# bms1.net
KiCad netlist of a schematic drawn in EAGLE
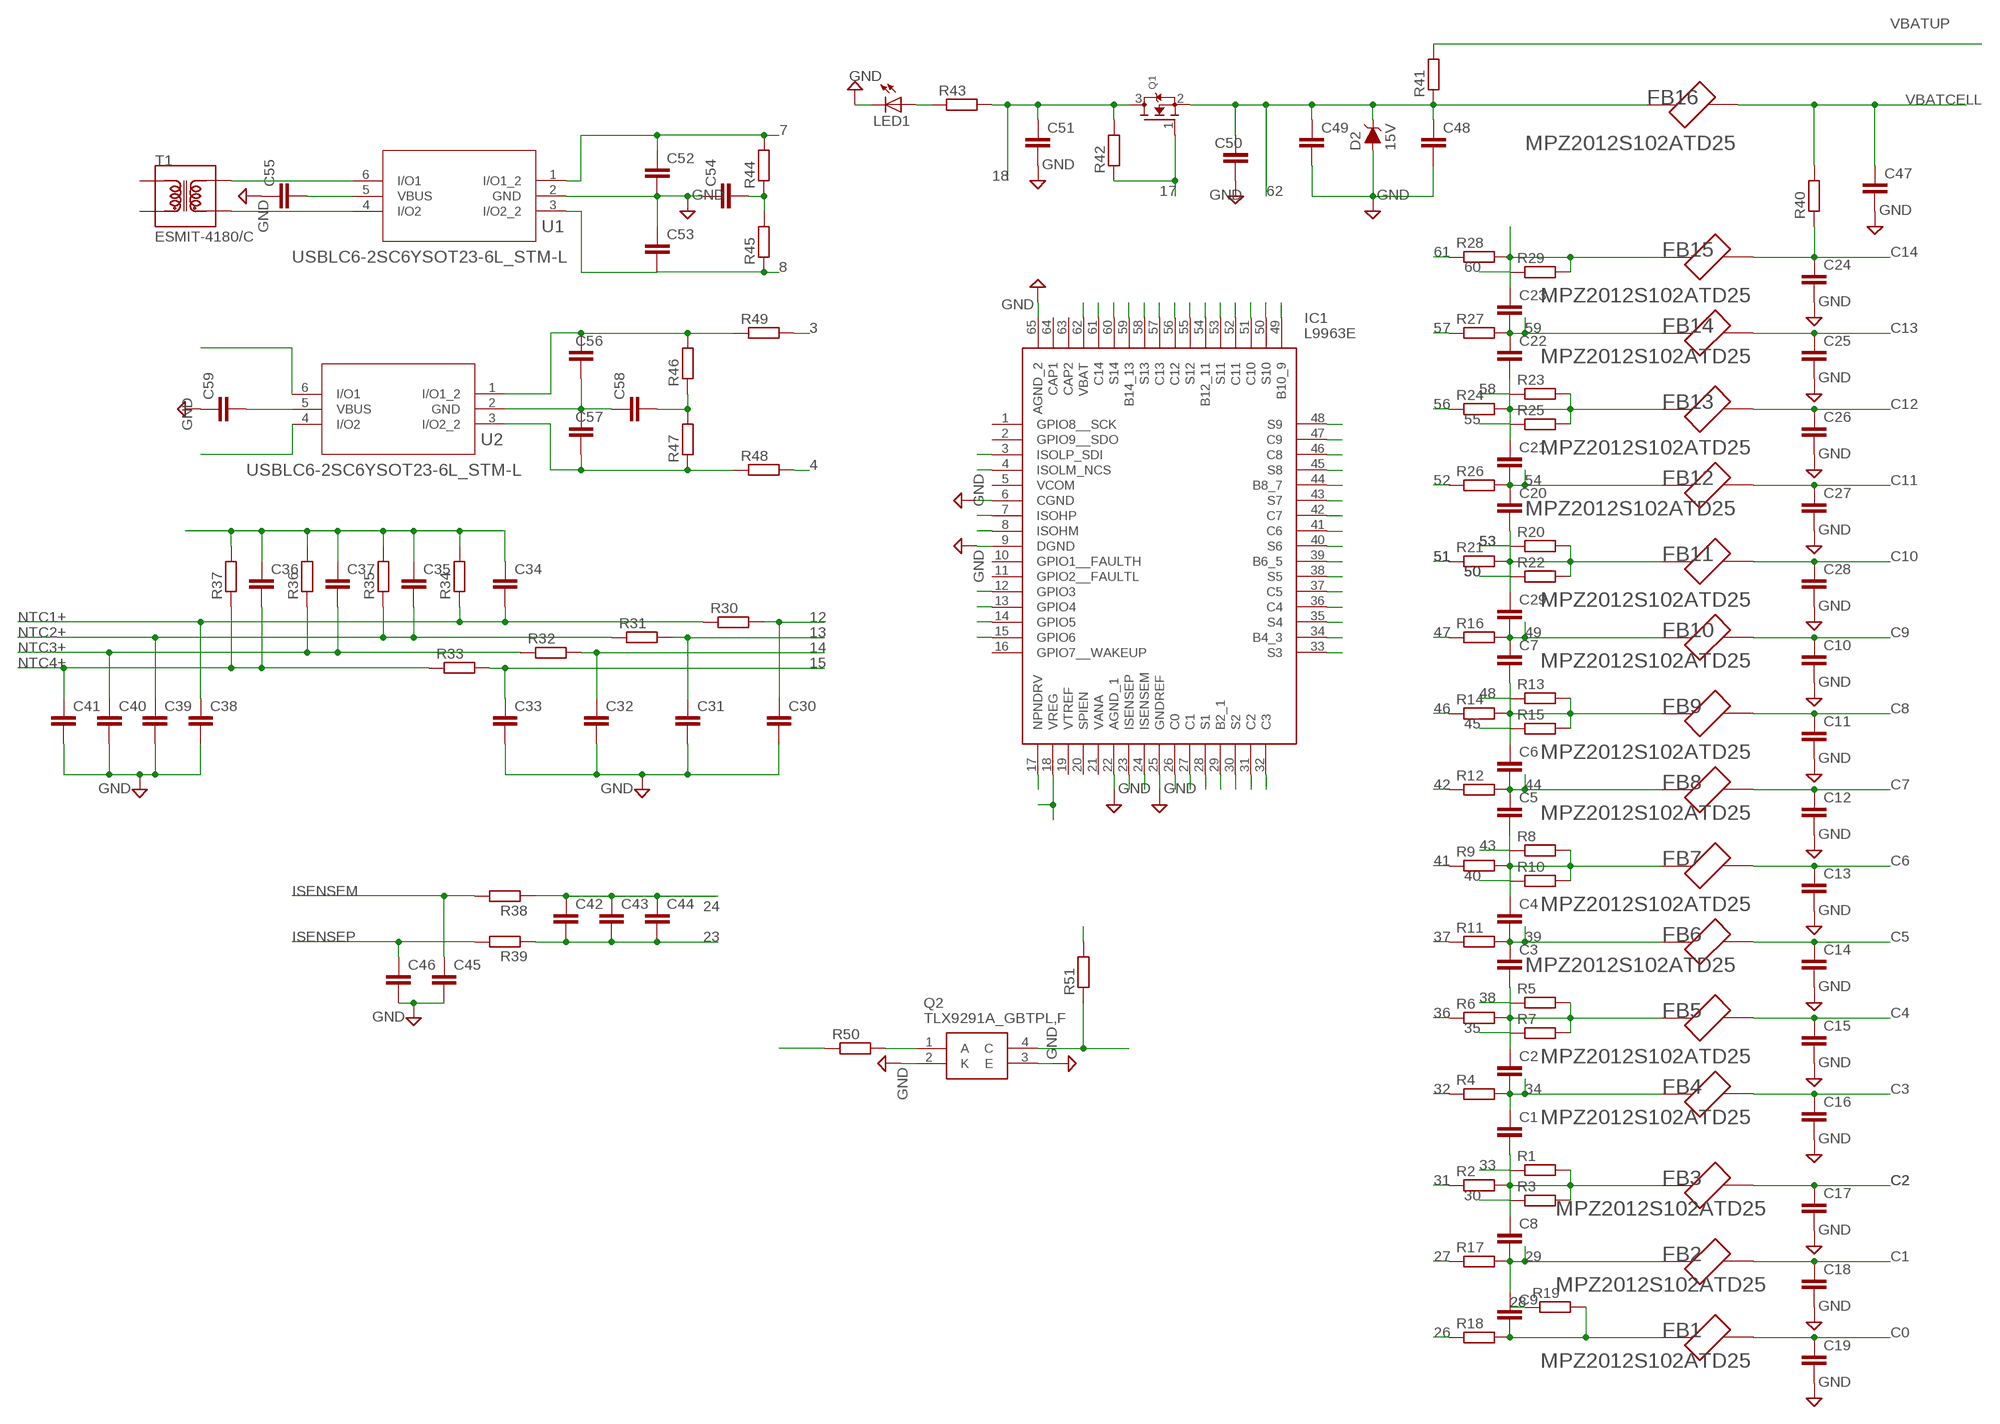
[diagram p0: schematic, sheet 1]

(export (version "E")
  (design (tool "Eeschema 10.0.6"))
  (components
    (comp (ref "C1")
      (value "C-EUC0402K")
      (footprint "eagle-import:C0402K")
      (libsource (lib "eagle-import") (part "C-EUC0402K"))
    )
    (comp (ref "C2")
      (value "C-EUC0402K")
      (footprint "eagle-import:C0402K")
      (libsource (lib "eagle-import") (part "C-EUC0402K"))
    )
    (comp (ref "C3")
      (value "C-EUC0402K")
      (footprint "eagle-import:C0402K")
      (libsource (lib "eagle-import") (part "C-EUC0402K"))
    )
    (comp (ref "C4")
      (value "C-EUC0402K")
      (footprint "eagle-import:C0402K")
      (libsource (lib "eagle-import") (part "C-EUC0402K"))
    )
    (comp (ref "C5")
      (value "C-EUC0402K")
      (footprint "eagle-import:C0402K")
      (libsource (lib "eagle-import") (part "C-EUC0402K"))
    )
    (comp (ref "C6")
      (value "C-EUC0402K")
      (footprint "eagle-import:C0402K")
      (libsource (lib "eagle-import") (part "C-EUC0402K"))
    )
    (comp (ref "C7")
      (value "C-EUC0402K")
      (footprint "eagle-import:C0402K")
      (libsource (lib "eagle-import") (part "C-EUC0402K"))
    )
    (comp (ref "C8")
      (value "C-EUC0402K")
      (footprint "eagle-import:C0402K")
      (libsource (lib "eagle-import") (part "C-EUC0402K"))
    )
    (comp (ref "C9")
      (value "C-EUC0402K")
      (footprint "eagle-import:C0402K")
      (libsource (lib "eagle-import") (part "C-EUC0402K"))
    )
    (comp (ref "C10")
      (value "C-EUC0402K")
      (footprint "eagle-import:C0402K")
      (libsource (lib "eagle-import") (part "C-EUC0402K"))
    )
    (comp (ref "C11")
      (value "C-EUC0402K")
      (footprint "eagle-import:C0402K")
      (libsource (lib "eagle-import") (part "C-EUC0402K"))
    )
    (comp (ref "C12")
      (value "C-EUC0402K")
      (footprint "eagle-import:C0402K")
      (libsource (lib "eagle-import") (part "C-EUC0402K"))
    )
    (comp (ref "C13")
      (value "C-EUC0402K")
      (footprint "eagle-import:C0402K")
      (libsource (lib "eagle-import") (part "C-EUC0402K"))
    )
    (comp (ref "C14")
      (value "C-EUC0402K")
      (footprint "eagle-import:C0402K")
      (libsource (lib "eagle-import") (part "C-EUC0402K"))
    )
    (comp (ref "C15")
      (value "C-EUC0402K")
      (footprint "eagle-import:C0402K")
      (libsource (lib "eagle-import") (part "C-EUC0402K"))
    )
    (comp (ref "C16")
      (value "C-EUC0402K")
      (footprint "eagle-import:C0402K")
      (libsource (lib "eagle-import") (part "C-EUC0402K"))
    )
    (comp (ref "C17")
      (value "C-EUC0402K")
      (footprint "eagle-import:C0402K")
      (libsource (lib "eagle-import") (part "C-EUC0402K"))
    )
    (comp (ref "C18")
      (value "C-EUC0402K")
      (footprint "eagle-import:C0402K")
      (libsource (lib "eagle-import") (part "C-EUC0402K"))
    )
    (comp (ref "C19")
      (value "C-EUC0402K")
      (footprint "eagle-import:C0402K")
      (libsource (lib "eagle-import") (part "C-EUC0402K"))
    )
    (comp (ref "C20")
      (value "C-EUC0402K")
      (footprint "eagle-import:C0402K")
      (libsource (lib "eagle-import") (part "C-EUC0402K"))
    )
    (comp (ref "C21")
      (value "C-EUC0402K")
      (footprint "eagle-import:C0402K")
      (libsource (lib "eagle-import") (part "C-EUC0402K"))
    )
    (comp (ref "C22")
      (value "C-EUC0402K")
      (footprint "eagle-import:C0402K")
      (libsource (lib "eagle-import") (part "C-EUC0402K"))
    )
    (comp (ref "C23")
      (value "C-EUC0402K")
      (footprint "eagle-import:C0402K")
      (libsource (lib "eagle-import") (part "C-EUC0402K"))
    )
    (comp (ref "C24")
      (value "C-EUC0402K")
      (footprint "eagle-import:C0402K")
      (libsource (lib "eagle-import") (part "C-EUC0402K"))
    )
    (comp (ref "C25")
      (value "C-EUC0402K")
      (footprint "eagle-import:C0402K")
      (libsource (lib "eagle-import") (part "C-EUC0402K"))
    )
    (comp (ref "C26")
      (value "C-EUC0402K")
      (footprint "eagle-import:C0402K")
      (libsource (lib "eagle-import") (part "C-EUC0402K"))
    )
    (comp (ref "C27")
      (value "C-EUC0402K")
      (footprint "eagle-import:C0402K")
      (libsource (lib "eagle-import") (part "C-EUC0402K"))
    )
    (comp (ref "C28")
      (value "C-EUC0402K")
      (footprint "eagle-import:C0402K")
      (libsource (lib "eagle-import") (part "C-EUC0402K"))
    )
    (comp (ref "C29")
      (value "C-EUC0402K")
      (footprint "eagle-import:C0402K")
      (libsource (lib "eagle-import") (part "C-EUC0402K"))
    )
    (comp (ref "C30")
      (value "C-EUC0402K")
      (footprint "eagle-import:C0402K")
      (libsource (lib "eagle-import") (part "C-EUC0402K"))
    )
    (comp (ref "C31")
      (value "C-EUC0402K")
      (footprint "eagle-import:C0402K")
      (libsource (lib "eagle-import") (part "C-EUC0402K"))
    )
    (comp (ref "C32")
      (value "C-EUC0402K")
      (footprint "eagle-import:C0402K")
      (libsource (lib "eagle-import") (part "C-EUC0402K"))
    )
    (comp (ref "C33")
      (value "C-EUC0402K")
      (footprint "eagle-import:C0402K")
      (libsource (lib "eagle-import") (part "C-EUC0402K"))
    )
    (comp (ref "C34")
      (value "C-EUC0402K")
      (footprint "eagle-import:C0402K")
      (libsource (lib "eagle-import") (part "C-EUC0402K"))
    )
    (comp (ref "C35")
      (value "C-EUC0402K")
      (footprint "eagle-import:C0402K")
      (libsource (lib "eagle-import") (part "C-EUC0402K"))
    )
    (comp (ref "C36")
      (value "C-EUC0402K")
      (footprint "eagle-import:C0402K")
      (libsource (lib "eagle-import") (part "C-EUC0402K"))
    )
    (comp (ref "C37")
      (value "C-EUC0402K")
      (footprint "eagle-import:C0402K")
      (libsource (lib "eagle-import") (part "C-EUC0402K"))
    )
    (comp (ref "C38")
      (value "C-EUC0402K")
      (footprint "eagle-import:C0402K")
      (libsource (lib "eagle-import") (part "C-EUC0402K"))
    )
    (comp (ref "C39")
      (value "C-EUC0402K")
      (footprint "eagle-import:C0402K")
      (libsource (lib "eagle-import") (part "C-EUC0402K"))
    )
    (comp (ref "C40")
      (value "C-EUC0402K")
      (footprint "eagle-import:C0402K")
      (libsource (lib "eagle-import") (part "C-EUC0402K"))
    )
    (comp (ref "C41")
      (value "C-EUC0402K")
      (footprint "eagle-import:C0402K")
      (libsource (lib "eagle-import") (part "C-EUC0402K"))
    )
    (comp (ref "C42")
      (value "C-EUC0402K")
      (footprint "eagle-import:C0402K")
      (libsource (lib "eagle-import") (part "C-EUC0402K"))
    )
    (comp (ref "C43")
      (value "C-EUC0402K")
      (footprint "eagle-import:C0402K")
      (libsource (lib "eagle-import") (part "C-EUC0402K"))
    )
    (comp (ref "C44")
      (value "C-EUC0402K")
      (footprint "eagle-import:C0402K")
      (libsource (lib "eagle-import") (part "C-EUC0402K"))
    )
    (comp (ref "C45")
      (value "C-EUC0402K")
      (footprint "eagle-import:C0402K")
      (libsource (lib "eagle-import") (part "C-EUC0402K"))
    )
    (comp (ref "C46")
      (value "C-EUC0402K")
      (footprint "eagle-import:C0402K")
      (libsource (lib "eagle-import") (part "C-EUC0402K"))
    )
    (comp (ref "C47")
      (value "C-EUC0402K")
      (footprint "eagle-import:C0402K")
      (libsource (lib "eagle-import") (part "C-EUC0402K"))
    )
    (comp (ref "C48")
      (value "C-EUC0402K")
      (footprint "eagle-import:C0402K")
      (libsource (lib "eagle-import") (part "C-EUC0402K"))
    )
    (comp (ref "C49")
      (value "C-EUC0402K")
      (footprint "eagle-import:C0402K")
      (libsource (lib "eagle-import") (part "C-EUC0402K"))
    )
    (comp (ref "C50")
      (value "C-EUC0402K")
      (footprint "eagle-import:C0402K")
      (libsource (lib "eagle-import") (part "C-EUC0402K"))
    )
    (comp (ref "C51")
      (value "C-EUC0402K")
      (footprint "eagle-import:C0402K")
      (libsource (lib "eagle-import") (part "C-EUC0402K"))
    )
    (comp (ref "C52")
      (value "C-EUC0402K")
      (footprint "eagle-import:C0402K")
      (libsource (lib "eagle-import") (part "C-EUC0402K"))
    )
    (comp (ref "C53")
      (value "C-EUC0402K")
      (footprint "eagle-import:C0402K")
      (libsource (lib "eagle-import") (part "C-EUC0402K"))
    )
    (comp (ref "C54")
      (value "C-EUC0402K")
      (footprint "eagle-import:C0402K")
      (libsource (lib "eagle-import") (part "C-EUC0402K"))
    )
    (comp (ref "C55")
      (value "C-EUC0402K")
      (footprint "eagle-import:C0402K")
      (libsource (lib "eagle-import") (part "C-EUC0402K"))
    )
    (comp (ref "C56")
      (value "C-EUC0402K")
      (footprint "eagle-import:C0402K")
      (libsource (lib "eagle-import") (part "C-EUC0402K"))
    )
    (comp (ref "C57")
      (value "C-EUC0402K")
      (footprint "eagle-import:C0402K")
      (libsource (lib "eagle-import") (part "C-EUC0402K"))
    )
    (comp (ref "C58")
      (value "C-EUC0402K")
      (footprint "eagle-import:C0402K")
      (libsource (lib "eagle-import") (part "C-EUC0402K"))
    )
    (comp (ref "C59")
      (value "C-EUC0402K")
      (footprint "eagle-import:C0402K")
      (libsource (lib "eagle-import") (part "C-EUC0402K"))
    )
    (comp (ref "D2")
      (value "15V")
      (footprint "eagle-import:PANASONIC_SMINI2-F5-B")
      (libsource (lib "eagle-import") (part "DIODE-ZENER-DZ2J150M0L"))
    )
    (comp (ref "FB1")
      (value "MPZ2012S102ATD25")
      (footprint "eagle-import:BEADC2012X105N")
      (fields (field (name "MF") "TDK"))
      (libsource (lib "eagle-import") (part "MPZ2012S102ATD25"))
    )
    (comp (ref "FB2")
      (value "MPZ2012S102ATD25")
      (footprint "eagle-import:BEADC2012X105N")
      (fields (field (name "MF") "TDK"))
      (libsource (lib "eagle-import") (part "MPZ2012S102ATD25"))
    )
    (comp (ref "FB3")
      (value "MPZ2012S102ATD25")
      (footprint "eagle-import:BEADC2012X105N")
      (fields (field (name "MF") "TDK"))
      (libsource (lib "eagle-import") (part "MPZ2012S102ATD25"))
    )
    (comp (ref "FB4")
      (value "MPZ2012S102ATD25")
      (footprint "eagle-import:BEADC2012X105N")
      (fields (field (name "MF") "TDK"))
      (libsource (lib "eagle-import") (part "MPZ2012S102ATD25"))
    )
    (comp (ref "FB5")
      (value "MPZ2012S102ATD25")
      (footprint "eagle-import:BEADC2012X105N")
      (fields (field (name "MF") "TDK"))
      (libsource (lib "eagle-import") (part "MPZ2012S102ATD25"))
    )
    (comp (ref "FB6")
      (value "MPZ2012S102ATD25")
      (footprint "eagle-import:BEADC2012X105N")
      (fields (field (name "MF") "TDK"))
      (libsource (lib "eagle-import") (part "MPZ2012S102ATD25"))
    )
    (comp (ref "FB7")
      (value "MPZ2012S102ATD25")
      (footprint "eagle-import:BEADC2012X105N")
      (fields (field (name "MF") "TDK"))
      (libsource (lib "eagle-import") (part "MPZ2012S102ATD25"))
    )
    (comp (ref "FB8")
      (value "MPZ2012S102ATD25")
      (footprint "eagle-import:BEADC2012X105N")
      (fields (field (name "MF") "TDK"))
      (libsource (lib "eagle-import") (part "MPZ2012S102ATD25"))
    )
    (comp (ref "FB9")
      (value "MPZ2012S102ATD25")
      (footprint "eagle-import:BEADC2012X105N")
      (fields (field (name "MF") "TDK"))
      (libsource (lib "eagle-import") (part "MPZ2012S102ATD25"))
    )
    (comp (ref "FB10")
      (value "MPZ2012S102ATD25")
      (footprint "eagle-import:BEADC2012X105N")
      (fields (field (name "MF") "TDK"))
      (libsource (lib "eagle-import") (part "MPZ2012S102ATD25"))
    )
    (comp (ref "FB11")
      (value "MPZ2012S102ATD25")
      (footprint "eagle-import:BEADC2012X105N")
      (fields (field (name "MF") "TDK"))
      (libsource (lib "eagle-import") (part "MPZ2012S102ATD25"))
    )
    (comp (ref "FB12")
      (value "MPZ2012S102ATD25")
      (footprint "eagle-import:BEADC2012X105N")
      (fields (field (name "MF") "TDK"))
      (libsource (lib "eagle-import") (part "MPZ2012S102ATD25"))
    )
    (comp (ref "FB13")
      (value "MPZ2012S102ATD25")
      (footprint "eagle-import:BEADC2012X105N")
      (fields (field (name "MF") "TDK"))
      (libsource (lib "eagle-import") (part "MPZ2012S102ATD25"))
    )
    (comp (ref "FB14")
      (value "MPZ2012S102ATD25")
      (footprint "eagle-import:BEADC2012X105N")
      (fields (field (name "MF") "TDK"))
      (libsource (lib "eagle-import") (part "MPZ2012S102ATD25"))
    )
    (comp (ref "FB15")
      (value "MPZ2012S102ATD25")
      (footprint "eagle-import:BEADC2012X105N")
      (fields (field (name "MF") "TDK"))
      (libsource (lib "eagle-import") (part "MPZ2012S102ATD25"))
    )
    (comp (ref "FB16")
      (value "MPZ2012S102ATD25")
      (footprint "eagle-import:BEADC2012X105N")
      (fields (field (name "MF") "TDK"))
      (libsource (lib "eagle-import") (part "MPZ2012S102ATD25"))
    )
    (comp (ref "IC1")
      (value "L9963E")
      (footprint "eagle-import:QFP50P1200X1200X120-65N")
      (fields (field (name "MOUSER_PART_NUMBER") "511-L9963E"))
      (libsource (lib "eagle-import") (part "L9963E"))
    )
    (comp (ref "LED1")
      (value "LED")
      (footprint "eagle-import:SMARTLED-TTW")
      (libsource (lib "eagle-import") (part "LED"))
    )
    (comp (ref "Q1")
      (value "MOSFET-NREFLOW")
      (footprint "eagle-import:SOT23")
      (libsource (lib "eagle-import") (part "MOSFET-NREFLOW"))
    )
    (comp (ref "Q2")
      (value "TLX9291A_GBTPL,F")
      (footprint "eagle-import:SOIC127P700X230-4N")
      (fields
        (field (name "MANUFACTURER_PART_NUMBER") "TLX9291A(GBTPL,F")
        (field (name "MOUSER_PART_NUMBER") "757-TLX9291AGBTPLF")
      )
      (libsource (lib "eagle-import") (part "TLX9291A_GBTPL,F"))
    )
    (comp (ref "R1")
      (value "R-EU_R0603")
      (footprint "eagle-import:R0603")
      (libsource (lib "eagle-import") (part "R-EU_R0603"))
    )
    (comp (ref "R2")
      (value "R-EU_R0603")
      (footprint "eagle-import:R0603")
      (libsource (lib "eagle-import") (part "R-EU_R0603"))
    )
    (comp (ref "R3")
      (value "R-EU_R0603")
      (footprint "eagle-import:R0603")
      (libsource (lib "eagle-import") (part "R-EU_R0603"))
    )
    (comp (ref "R4")
      (value "R-EU_R0603")
      (footprint "eagle-import:R0603")
      (libsource (lib "eagle-import") (part "R-EU_R0603"))
    )
    (comp (ref "R5")
      (value "R-EU_R0603")
      (footprint "eagle-import:R0603")
      (libsource (lib "eagle-import") (part "R-EU_R0603"))
    )
    (comp (ref "R6")
      (value "R-EU_R0603")
      (footprint "eagle-import:R0603")
      (libsource (lib "eagle-import") (part "R-EU_R0603"))
    )
    (comp (ref "R7")
      (value "R-EU_R0603")
      (footprint "eagle-import:R0603")
      (libsource (lib "eagle-import") (part "R-EU_R0603"))
    )
    (comp (ref "R8")
      (value "R-EU_R0603")
      (footprint "eagle-import:R0603")
      (libsource (lib "eagle-import") (part "R-EU_R0603"))
    )
    (comp (ref "R9")
      (value "R-EU_R0603")
      (footprint "eagle-import:R0603")
      (libsource (lib "eagle-import") (part "R-EU_R0603"))
    )
    (comp (ref "R10")
      (value "R-EU_R0603")
      (footprint "eagle-import:R0603")
      (libsource (lib "eagle-import") (part "R-EU_R0603"))
    )
    (comp (ref "R11")
      (value "R-EU_R0603")
      (footprint "eagle-import:R0603")
      (libsource (lib "eagle-import") (part "R-EU_R0603"))
    )
    (comp (ref "R12")
      (value "R-EU_R0603")
      (footprint "eagle-import:R0603")
      (libsource (lib "eagle-import") (part "R-EU_R0603"))
    )
    (comp (ref "R13")
      (value "R-EU_R0603")
      (footprint "eagle-import:R0603")
      (libsource (lib "eagle-import") (part "R-EU_R0603"))
    )
    (comp (ref "R14")
      (value "R-EU_R0603")
      (footprint "eagle-import:R0603")
      (libsource (lib "eagle-import") (part "R-EU_R0603"))
    )
    (comp (ref "R15")
      (value "R-EU_R0603")
      (footprint "eagle-import:R0603")
      (libsource (lib "eagle-import") (part "R-EU_R0603"))
    )
    (comp (ref "R16")
      (value "R-EU_R0603")
      (footprint "eagle-import:R0603")
      (libsource (lib "eagle-import") (part "R-EU_R0603"))
    )
    (comp (ref "R17")
      (value "R-EU_R0603")
      (footprint "eagle-import:R0603")
      (libsource (lib "eagle-import") (part "R-EU_R0603"))
    )
    (comp (ref "R18")
      (value "R-EU_R0603")
      (footprint "eagle-import:R0603")
      (libsource (lib "eagle-import") (part "R-EU_R0603"))
    )
    (comp (ref "R19")
      (value "R-EU_R0603")
      (footprint "eagle-import:R0603")
      (libsource (lib "eagle-import") (part "R-EU_R0603"))
    )
    (comp (ref "R20")
      (value "R-EU_R0603")
      (footprint "eagle-import:R0603")
      (libsource (lib "eagle-import") (part "R-EU_R0603"))
    )
    (comp (ref "R21")
      (value "R-EU_R0603")
      (footprint "eagle-import:R0603")
      (libsource (lib "eagle-import") (part "R-EU_R0603"))
    )
    (comp (ref "R22")
      (value "R-EU_R0603")
      (footprint "eagle-import:R0603")
      (libsource (lib "eagle-import") (part "R-EU_R0603"))
    )
    (comp (ref "R23")
      (value "R-EU_R0603")
      (footprint "eagle-import:R0603")
      (libsource (lib "eagle-import") (part "R-EU_R0603"))
    )
    (comp (ref "R24")
      (value "R-EU_R0603")
      (footprint "eagle-import:R0603")
      (libsource (lib "eagle-import") (part "R-EU_R0603"))
    )
    (comp (ref "R25")
      (value "R-EU_R0603")
      (footprint "eagle-import:R0603")
      (libsource (lib "eagle-import") (part "R-EU_R0603"))
    )
    (comp (ref "R26")
      (value "R-EU_R0603")
      (footprint "eagle-import:R0603")
      (libsource (lib "eagle-import") (part "R-EU_R0603"))
    )
    (comp (ref "R27")
      (value "R-EU_R0603")
      (footprint "eagle-import:R0603")
      (libsource (lib "eagle-import") (part "R-EU_R0603"))
    )
    (comp (ref "R28")
      (value "R-EU_R0603")
      (footprint "eagle-import:R0603")
      (libsource (lib "eagle-import") (part "R-EU_R0603"))
    )
    (comp (ref "R29")
      (value "R-EU_R0603")
      (footprint "eagle-import:R0603")
      (libsource (lib "eagle-import") (part "R-EU_R0603"))
    )
    (comp (ref "R30")
      (value "R-EU_R0603")
      (footprint "eagle-import:R0603")
      (libsource (lib "eagle-import") (part "R-EU_R0603"))
    )
    (comp (ref "R31")
      (value "R-EU_R0603")
      (footprint "eagle-import:R0603")
      (libsource (lib "eagle-import") (part "R-EU_R0603"))
    )
    (comp (ref "R32")
      (value "R-EU_R0603")
      (footprint "eagle-import:R0603")
      (libsource (lib "eagle-import") (part "R-EU_R0603"))
    )
    (comp (ref "R33")
      (value "R-EU_R0603")
      (footprint "eagle-import:R0603")
      (libsource (lib "eagle-import") (part "R-EU_R0603"))
    )
    (comp (ref "R34")
      (value "R-EU_R0603")
      (footprint "eagle-import:R0603")
      (libsource (lib "eagle-import") (part "R-EU_R0603"))
    )
    (comp (ref "R35")
      (value "R-EU_R0603")
      (footprint "eagle-import:R0603")
      (libsource (lib "eagle-import") (part "R-EU_R0603"))
    )
    (comp (ref "R36")
      (value "R-EU_R0603")
      (footprint "eagle-import:R0603")
      (libsource (lib "eagle-import") (part "R-EU_R0603"))
    )
    (comp (ref "R37")
      (value "R-EU_R0603")
      (footprint "eagle-import:R0603")
      (libsource (lib "eagle-import") (part "R-EU_R0603"))
    )
    (comp (ref "R38")
      (value "R-EU_R0603")
      (footprint "eagle-import:R0603")
      (libsource (lib "eagle-import") (part "R-EU_R0603"))
    )
    (comp (ref "R39")
      (value "R-EU_R0603")
      (footprint "eagle-import:R0603")
      (libsource (lib "eagle-import") (part "R-EU_R0603"))
    )
    (comp (ref "R40")
      (value "R-EU_R0603")
      (footprint "eagle-import:R0603")
      (libsource (lib "eagle-import") (part "R-EU_R0603"))
    )
    (comp (ref "R41")
      (value "R-EU_R0603")
      (footprint "eagle-import:R0603")
      (libsource (lib "eagle-import") (part "R-EU_R0603"))
    )
    (comp (ref "R42")
      (value "R-EU_R0603")
      (footprint "eagle-import:R0603")
      (libsource (lib "eagle-import") (part "R-EU_R0603"))
    )
    (comp (ref "R43")
      (value "R-EU_R0603")
      (footprint "eagle-import:R0603")
      (libsource (lib "eagle-import") (part "R-EU_R0603"))
    )
    (comp (ref "R44")
      (value "R-EU_R0603")
      (footprint "eagle-import:R0603")
      (libsource (lib "eagle-import") (part "R-EU_R0603"))
    )
    (comp (ref "R45")
      (value "R-EU_R0603")
      (footprint "eagle-import:R0603")
      (libsource (lib "eagle-import") (part "R-EU_R0603"))
    )
    (comp (ref "R46")
      (value "R-EU_R0603")
      (footprint "eagle-import:R0603")
      (libsource (lib "eagle-import") (part "R-EU_R0603"))
    )
    (comp (ref "R47")
      (value "R-EU_R0603")
      (footprint "eagle-import:R0603")
      (libsource (lib "eagle-import") (part "R-EU_R0603"))
    )
    (comp (ref "R48")
      (value "R-EU_R0603")
      (footprint "eagle-import:R0603")
      (libsource (lib "eagle-import") (part "R-EU_R0603"))
    )
    (comp (ref "R49")
      (value "R-EU_R0603")
      (footprint "eagle-import:R0603")
      (libsource (lib "eagle-import") (part "R-EU_R0603"))
    )
    (comp (ref "R50")
      (value "R-EU_M0805")
      (footprint "eagle-import:M0805")
      (libsource (lib "eagle-import") (part "R-EU_M0805"))
    )
    (comp (ref "R51")
      (value "R-EU_M0805")
      (footprint "eagle-import:M0805")
      (libsource (lib "eagle-import") (part "R-EU_M0805"))
    )
    (comp (ref "T1")
      (value "ESMIT-4180/C")
      (footprint "eagle-import:XFMR_ESMIT-4180_C")
      (fields (field (name "MF") "Sumida America"))
      (libsource (lib "eagle-import") (part "ESMIT-4180/C"))
    )
    (comp (ref "U1")
      (value "USBLC6-2SC6YSOT23-6L_STM-L")
      (footprint "eagle-import:SOT23-6L_STM-L")
      (fields
        (field (name "MANUFACTURER_PART_NUMBER") "USBLC6-2SC6Y")
        (field (name "COPYRIGHT") "Copyright (C) 2021 Ultra Librarian. All rights reserved.")
      )
      (libsource (lib "eagle-import") (part "USBLC6-2SC6YSOT23-6L_STM-L"))
    )
    (comp (ref "U2")
      (value "USBLC6-2SC6YSOT23-6L_STM-L")
      (footprint "eagle-import:SOT23-6L_STM-L")
      (fields
        (field (name "MANUFACTURER_PART_NUMBER") "USBLC6-2SC6Y")
        (field (name "COPYRIGHT") "Copyright (C) 2021 Ultra Librarian. All rights reserved.")
      )
      (libsource (lib "eagle-import") (part "USBLC6-2SC6YSOT23-6L_STM-L"))
    )
  )
  (nets
    (net (code "1") (name "/3") (class "Default")
      (node (ref "IC1") (pin "3") (pinfunction "ISOLP_SDI_3") (pintype "bidirectional"))
      (node (ref "R49") (pin "2") (pinfunction "2_2") (pintype "passive"))
    )
    (net (code "2") (name "/4") (class "Default")
      (node (ref "IC1") (pin "4") (pinfunction "ISOLM_NCS_4") (pintype "bidirectional"))
      (node (ref "R48") (pin "2") (pinfunction "2_2") (pintype "passive"))
    )
    (net (code "3") (name "/7") (class "Default")
      (node (ref "C52") (pin "1") (pinfunction "1_1") (pintype "passive"))
      (node (ref "IC1") (pin "7") (pinfunction "ISOHP_7") (pintype "bidirectional"))
      (node (ref "R44") (pin "2") (pinfunction "2_2") (pintype "passive"))
      (node (ref "U1") (pin "1") (pinfunction "I/O1_2_1") (pintype "bidirectional"))
    )
    (net (code "4") (name "/8") (class "Default")
      (node (ref "C53") (pin "2") (pinfunction "2_2") (pintype "passive"))
      (node (ref "IC1") (pin "8") (pinfunction "ISOHM_8") (pintype "bidirectional"))
      (node (ref "R45") (pin "1") (pinfunction "1_1") (pintype "passive"))
      (node (ref "U1") (pin "3") (pinfunction "I/O2_2_3") (pintype "bidirectional"))
    )
    (net (code "5") (name "/12") (class "Default")
      (node (ref "C30") (pin "1") (pinfunction "1_1") (pintype "passive"))
      (node (ref "IC1") (pin "12") (pinfunction "GPIO3_12") (pintype "bidirectional"))
      (node (ref "R30") (pin "2") (pinfunction "2_2") (pintype "passive"))
    )
    (net (code "6") (name "/13") (class "Default")
      (node (ref "C31") (pin "1") (pinfunction "1_1") (pintype "passive"))
      (node (ref "IC1") (pin "13") (pinfunction "GPIO4_13") (pintype "bidirectional"))
      (node (ref "R31") (pin "2") (pinfunction "2_2") (pintype "passive"))
    )
    (net (code "7") (name "/14") (class "Default")
      (node (ref "C32") (pin "1") (pinfunction "1_1") (pintype "passive"))
      (node (ref "IC1") (pin "14") (pinfunction "GPIO5_14") (pintype "bidirectional"))
      (node (ref "R32") (pin "2") (pinfunction "2_2") (pintype "passive"))
    )
    (net (code "8") (name "/15") (class "Default")
      (node (ref "C33") (pin "1") (pinfunction "1_1") (pintype "passive"))
      (node (ref "IC1") (pin "15") (pinfunction "GPIO6_15") (pintype "bidirectional"))
      (node (ref "R33") (pin "2") (pinfunction "2_2") (pintype "passive"))
    )
    (net (code "9") (name "/17") (class "Default")
      (node (ref "IC1") (pin "17") (pinfunction "NPNDRV_17") (pintype "bidirectional"))
      (node (ref "Q1") (pin "1") (pinfunction "G_1") (pintype "bidirectional"))
      (node (ref "R42") (pin "1") (pinfunction "1_1") (pintype "passive"))
    )
    (net (code "10") (name "/18") (class "Default")
      (node (ref "C51") (pin "1") (pinfunction "1_1") (pintype "passive"))
      (node (ref "Q1") (pin "3") (pinfunction "D_3") (pintype "bidirectional"))
      (node (ref "R42") (pin "2") (pinfunction "2_2") (pintype "passive"))
      (node (ref "R43") (pin "2") (pinfunction "2_2") (pintype "passive"))
    )
    (net (code "11") (name "/23") (class "Default")
      (node (ref "C42") (pin "2") (pinfunction "2_2") (pintype "passive"))
      (node (ref "C43") (pin "2") (pinfunction "2_2") (pintype "passive"))
      (node (ref "C44") (pin "2") (pinfunction "2_2") (pintype "passive"))
      (node (ref "IC1") (pin "23") (pinfunction "ISENSEP_23") (pintype "bidirectional"))
      (node (ref "R39") (pin "1") (pinfunction "1_1") (pintype "passive"))
    )
    (net (code "12") (name "/24") (class "Default")
      (node (ref "C42") (pin "1") (pinfunction "1_1") (pintype "passive"))
      (node (ref "C43") (pin "1") (pinfunction "1_1") (pintype "passive"))
      (node (ref "C44") (pin "1") (pinfunction "1_1") (pintype "passive"))
      (node (ref "IC1") (pin "24") (pinfunction "ISENSEM_24") (pintype "bidirectional"))
      (node (ref "R38") (pin "1") (pinfunction "1_1") (pintype "passive"))
    )
    (net (code "13") (name "/26") (class "Default")
      (node (ref "IC1") (pin "26") (pinfunction "C0_26") (pintype "bidirectional"))
      (node (ref "R18") (pin "1") (pinfunction "1_1") (pintype "passive"))
    )
    (net (code "14") (name "/27") (class "Default")
      (node (ref "IC1") (pin "27") (pinfunction "C1_27") (pintype "bidirectional"))
      (node (ref "R17") (pin "1") (pinfunction "1_1") (pintype "passive"))
    )
    (net (code "15") (name "/28") (class "Default")
      (node (ref "IC1") (pin "28") (pinfunction "S1_28") (pintype "bidirectional"))
      (node (ref "R19") (pin "1") (pinfunction "1_1") (pintype "passive"))
    )
    (net (code "16") (name "/29") (class "Default")
      (node (ref "C8") (pin "2") (pinfunction "2_2") (pintype "passive"))
      (node (ref "C9") (pin "1") (pinfunction "1_1") (pintype "passive"))
      (node (ref "FB2") (pin "1") (pinfunction "1_1") (pintype "passive"))
      (node (ref "IC1") (pin "29") (pinfunction "B2_1_29") (pintype "bidirectional"))
      (node (ref "R17") (pin "2") (pinfunction "2_2") (pintype "passive"))
    )
    (net (code "17") (name "/30") (class "Default")
      (node (ref "IC1") (pin "30") (pinfunction "S2_30") (pintype "bidirectional"))
      (node (ref "R3") (pin "1") (pinfunction "1_1") (pintype "passive"))
    )
    (net (code "18") (name "/31") (class "Default")
      (node (ref "IC1") (pin "31") (pinfunction "C2_31") (pintype "bidirectional"))
      (node (ref "R2") (pin "1") (pinfunction "1_1") (pintype "passive"))
    )
    (net (code "19") (name "/32") (class "Default")
      (node (ref "IC1") (pin "32") (pinfunction "C3_32") (pintype "bidirectional"))
      (node (ref "R4") (pin "1") (pinfunction "1_1") (pintype "passive"))
    )
    (net (code "20") (name "/33") (class "Default")
      (node (ref "IC1") (pin "33") (pinfunction "S3_33") (pintype "bidirectional"))
      (node (ref "R1") (pin "1") (pinfunction "1_1") (pintype "passive"))
    )
    (net (code "21") (name "/34") (class "Default")
      (node (ref "C1") (pin "1") (pinfunction "1_1") (pintype "passive"))
      (node (ref "C2") (pin "2") (pinfunction "2_2") (pintype "passive"))
      (node (ref "C9") (pin "2") (pinfunction "2_2") (pintype "passive"))
      (node (ref "FB1") (pin "1") (pinfunction "1_1") (pintype "passive"))
      (node (ref "FB4") (pin "1") (pinfunction "1_1") (pintype "passive"))
      (node (ref "IC1") (pin "34") (pinfunction "B4_3_34") (pintype "bidirectional"))
      (node (ref "R18") (pin "2") (pinfunction "2_2") (pintype "passive"))
      (node (ref "R19") (pin "2") (pinfunction "2_2") (pintype "passive"))
      (node (ref "R4") (pin "2") (pinfunction "2_2") (pintype "passive"))
    )
    (net (code "22") (name "/35") (class "Default")
      (node (ref "IC1") (pin "35") (pinfunction "S4_35") (pintype "bidirectional"))
      (node (ref "R7") (pin "1") (pinfunction "1_1") (pintype "passive"))
    )
    (net (code "23") (name "/36") (class "Default")
      (node (ref "IC1") (pin "36") (pinfunction "C4_36") (pintype "bidirectional"))
      (node (ref "R6") (pin "1") (pinfunction "1_1") (pintype "passive"))
    )
    (net (code "24") (name "/37") (class "Default")
      (node (ref "IC1") (pin "37") (pinfunction "C5_37") (pintype "bidirectional"))
      (node (ref "R11") (pin "1") (pinfunction "1_1") (pintype "passive"))
    )
    (net (code "25") (name "/38") (class "Default")
      (node (ref "IC1") (pin "38") (pinfunction "S5_38") (pintype "bidirectional"))
      (node (ref "R5") (pin "1") (pinfunction "1_1") (pintype "passive"))
    )
    (net (code "26") (name "/39") (class "Default")
      (node (ref "C3") (pin "1") (pinfunction "1_1") (pintype "passive"))
      (node (ref "C4") (pin "2") (pinfunction "2_2") (pintype "passive"))
      (node (ref "FB6") (pin "1") (pinfunction "1_1") (pintype "passive"))
      (node (ref "IC1") (pin "39") (pinfunction "B6_5_39") (pintype "bidirectional"))
      (node (ref "R11") (pin "2") (pinfunction "2_2") (pintype "passive"))
    )
    (net (code "27") (name "/40") (class "Default")
      (node (ref "IC1") (pin "40") (pinfunction "S6_40") (pintype "bidirectional"))
      (node (ref "R10") (pin "1") (pinfunction "1_1") (pintype "passive"))
    )
    (net (code "28") (name "/41") (class "Default")
      (node (ref "IC1") (pin "41") (pinfunction "C6_41") (pintype "bidirectional"))
      (node (ref "R9") (pin "1") (pinfunction "1_1") (pintype "passive"))
    )
    (net (code "29") (name "/42") (class "Default")
      (node (ref "IC1") (pin "42") (pinfunction "C7_42") (pintype "bidirectional"))
      (node (ref "R12") (pin "1") (pinfunction "1_1") (pintype "passive"))
    )
    (net (code "30") (name "/43") (class "Default")
      (node (ref "IC1") (pin "43") (pinfunction "S7_43") (pintype "bidirectional"))
      (node (ref "R8") (pin "1") (pinfunction "1_1") (pintype "passive"))
    )
    (net (code "31") (name "/44") (class "Default")
      (node (ref "C5") (pin "1") (pinfunction "1_1") (pintype "passive"))
      (node (ref "C6") (pin "2") (pinfunction "2_2") (pintype "passive"))
      (node (ref "FB8") (pin "1") (pinfunction "1_1") (pintype "passive"))
      (node (ref "IC1") (pin "44") (pinfunction "B8_7_44") (pintype "bidirectional"))
      (node (ref "R12") (pin "2") (pinfunction "2_2") (pintype "passive"))
    )
    (net (code "32") (name "/45") (class "Default")
      (node (ref "IC1") (pin "45") (pinfunction "S8_45") (pintype "bidirectional"))
      (node (ref "R15") (pin "1") (pinfunction "1_1") (pintype "passive"))
    )
    (net (code "33") (name "/46") (class "Default")
      (node (ref "IC1") (pin "46") (pinfunction "C8_46") (pintype "bidirectional"))
      (node (ref "R14") (pin "1") (pinfunction "1_1") (pintype "passive"))
    )
    (net (code "34") (name "/47") (class "Default")
      (node (ref "IC1") (pin "47") (pinfunction "C9_47") (pintype "bidirectional"))
      (node (ref "R16") (pin "1") (pinfunction "1_1") (pintype "passive"))
    )
    (net (code "35") (name "/48") (class "Default")
      (node (ref "IC1") (pin "48") (pinfunction "S9_48") (pintype "bidirectional"))
      (node (ref "R13") (pin "1") (pinfunction "1_1") (pintype "passive"))
    )
    (net (code "36") (name "/49") (class "Default")
      (node (ref "C29") (pin "2") (pinfunction "2_2") (pintype "passive"))
      (node (ref "C7") (pin "1") (pinfunction "1_1") (pintype "passive"))
      (node (ref "FB10") (pin "1") (pinfunction "1_1") (pintype "passive"))
      (node (ref "IC1") (pin "49") (pinfunction "B10_9_49") (pintype "bidirectional"))
      (node (ref "R16") (pin "2") (pinfunction "2_2") (pintype "passive"))
    )
    (net (code "37") (name "/50") (class "Default")
      (node (ref "IC1") (pin "50") (pinfunction "S10_50") (pintype "bidirectional"))
      (node (ref "R22") (pin "1") (pinfunction "1_1") (pintype "passive"))
    )
    (net (code "38") (name "/51") (class "Default")
      (node (ref "IC1") (pin "51") (pinfunction "C10_51") (pintype "bidirectional"))
      (node (ref "R21") (pin "1") (pinfunction "1_1") (pintype "passive"))
    )
    (net (code "39") (name "/52") (class "Default")
      (node (ref "IC1") (pin "52") (pinfunction "C11_52") (pintype "bidirectional"))
      (node (ref "R26") (pin "1") (pinfunction "1_1") (pintype "passive"))
    )
    (net (code "40") (name "/53") (class "Default")
      (node (ref "IC1") (pin "53") (pinfunction "S11_53") (pintype "bidirectional"))
      (node (ref "R20") (pin "1") (pinfunction "1_1") (pintype "passive"))
    )
    (net (code "41") (name "/54") (class "Default")
      (node (ref "C20") (pin "1") (pinfunction "1_1") (pintype "passive"))
      (node (ref "C21") (pin "2") (pinfunction "2_2") (pintype "passive"))
      (node (ref "FB12") (pin "1") (pinfunction "1_1") (pintype "passive"))
      (node (ref "IC1") (pin "54") (pinfunction "B12_11_54") (pintype "bidirectional"))
      (node (ref "R26") (pin "2") (pinfunction "2_2") (pintype "passive"))
    )
    (net (code "42") (name "/55") (class "Default")
      (node (ref "IC1") (pin "55") (pinfunction "S12_55") (pintype "bidirectional"))
      (node (ref "R25") (pin "1") (pinfunction "1_1") (pintype "passive"))
    )
    (net (code "43") (name "/56") (class "Default")
      (node (ref "IC1") (pin "56") (pinfunction "C12_56") (pintype "bidirectional"))
      (node (ref "R24") (pin "1") (pinfunction "1_1") (pintype "passive"))
    )
    (net (code "44") (name "/57") (class "Default")
      (node (ref "IC1") (pin "57") (pinfunction "C13_57") (pintype "bidirectional"))
      (node (ref "R27") (pin "1") (pinfunction "1_1") (pintype "passive"))
    )
    (net (code "45") (name "/58") (class "Default")
      (node (ref "IC1") (pin "58") (pinfunction "S13_58") (pintype "bidirectional"))
      (node (ref "R23") (pin "1") (pinfunction "1_1") (pintype "passive"))
    )
    (net (code "46") (name "/59") (class "Default")
      (node (ref "C22") (pin "1") (pinfunction "1_1") (pintype "passive"))
      (node (ref "C23") (pin "2") (pinfunction "2_2") (pintype "passive"))
      (node (ref "FB14") (pin "1") (pinfunction "1_1") (pintype "passive"))
      (node (ref "IC1") (pin "59") (pinfunction "B14_13_59") (pintype "bidirectional"))
      (node (ref "R27") (pin "2") (pinfunction "2_2") (pintype "passive"))
    )
    (net (code "47") (name "/60") (class "Default")
      (node (ref "IC1") (pin "60") (pinfunction "S14_60") (pintype "bidirectional"))
      (node (ref "R29") (pin "1") (pinfunction "1_1") (pintype "passive"))
    )
    (net (code "48") (name "/61") (class "Default")
      (node (ref "IC1") (pin "61") (pinfunction "C14_61") (pintype "bidirectional"))
      (node (ref "R28") (pin "1") (pinfunction "1_1") (pintype "passive"))
    )
    (net (code "49") (name "/62") (class "Default")
      (node (ref "C48") (pin "1") (pinfunction "1_1") (pintype "passive"))
      (node (ref "C49") (pin "1") (pinfunction "1_1") (pintype "passive"))
      (node (ref "C50") (pin "1") (pinfunction "1_1") (pintype "passive"))
      (node (ref "D2") (pin "C") (pinfunction "C_C") (pintype "passive"))
      (node (ref "FB16") (pin "1") (pinfunction "1_1") (pintype "passive"))
      (node (ref "IC1") (pin "62") (pinfunction "VBAT_62") (pintype "bidirectional"))
      (node (ref "Q1") (pin "2") (pinfunction "S_2") (pintype "bidirectional"))
      (node (ref "R41") (pin "1") (pinfunction "1_1") (pintype "passive"))
    )
    (net (code "50") (name "/C0") (class "Default")
      (node (ref "C19") (pin "1") (pinfunction "1_1") (pintype "passive"))
      (node (ref "FB1") (pin "2") (pinfunction "2_2") (pintype "passive"))
    )
    (net (code "51") (name "/C1") (class "Default")
      (node (ref "C18") (pin "1") (pinfunction "1_1") (pintype "passive"))
      (node (ref "FB2") (pin "2") (pinfunction "2_2") (pintype "passive"))
    )
    (net (code "52") (name "/C2") (class "Default")
      (node (ref "C17") (pin "1") (pinfunction "1_1") (pintype "passive"))
      (node (ref "FB3") (pin "2") (pinfunction "2_2") (pintype "passive"))
    )
    (net (code "53") (name "/C3") (class "Default")
      (node (ref "C16") (pin "1") (pinfunction "1_1") (pintype "passive"))
      (node (ref "FB4") (pin "2") (pinfunction "2_2") (pintype "passive"))
    )
    (net (code "54") (name "/C4") (class "Default")
      (node (ref "C15") (pin "1") (pinfunction "1_1") (pintype "passive"))
      (node (ref "FB5") (pin "2") (pinfunction "2_2") (pintype "passive"))
    )
    (net (code "55") (name "/C5") (class "Default")
      (node (ref "C14") (pin "1") (pinfunction "1_1") (pintype "passive"))
      (node (ref "FB6") (pin "2") (pinfunction "2_2") (pintype "passive"))
    )
    (net (code "56") (name "/C6") (class "Default")
      (node (ref "C13") (pin "1") (pinfunction "1_1") (pintype "passive"))
      (node (ref "FB7") (pin "2") (pinfunction "2_2") (pintype "passive"))
    )
    (net (code "57") (name "/C7") (class "Default")
      (node (ref "C12") (pin "1") (pinfunction "1_1") (pintype "passive"))
      (node (ref "FB8") (pin "2") (pinfunction "2_2") (pintype "passive"))
    )
    (net (code "58") (name "/C8") (class "Default")
      (node (ref "C11") (pin "1") (pinfunction "1_1") (pintype "passive"))
      (node (ref "FB9") (pin "2") (pinfunction "2_2") (pintype "passive"))
    )
    (net (code "59") (name "/C9") (class "Default")
      (node (ref "C10") (pin "1") (pinfunction "1_1") (pintype "passive"))
      (node (ref "FB10") (pin "2") (pinfunction "2_2") (pintype "passive"))
    )
    (net (code "60") (name "/C10") (class "Default")
      (node (ref "C28") (pin "1") (pinfunction "1_1") (pintype "passive"))
      (node (ref "FB11") (pin "2") (pinfunction "2_2") (pintype "passive"))
    )
    (net (code "61") (name "/C11") (class "Default")
      (node (ref "C27") (pin "1") (pinfunction "1_1") (pintype "passive"))
      (node (ref "FB12") (pin "2") (pinfunction "2_2") (pintype "passive"))
    )
    (net (code "62") (name "/C12") (class "Default")
      (node (ref "C26") (pin "1") (pinfunction "1_1") (pintype "passive"))
      (node (ref "FB13") (pin "2") (pinfunction "2_2") (pintype "passive"))
    )
    (net (code "63") (name "/C13") (class "Default")
      (node (ref "C25") (pin "1") (pinfunction "1_1") (pintype "passive"))
      (node (ref "FB14") (pin "2") (pinfunction "2_2") (pintype "passive"))
    )
    (net (code "64") (name "/C14") (class "Default")
      (node (ref "C24") (pin "1") (pinfunction "1_1") (pintype "passive"))
      (node (ref "FB15") (pin "2") (pinfunction "2_2") (pintype "passive"))
      (node (ref "R40") (pin "1") (pinfunction "1_1") (pintype "passive"))
    )
    (net (code "65") (name "/ISENSEM") (class "Default")
      (node (ref "C45") (pin "1") (pinfunction "1_1") (pintype "passive"))
      (node (ref "R38") (pin "2") (pinfunction "2_2") (pintype "passive"))
    )
    (net (code "66") (name "/ISENSEP") (class "Default")
      (node (ref "C46") (pin "1") (pinfunction "1_1") (pintype "passive"))
      (node (ref "R39") (pin "2") (pinfunction "2_2") (pintype "passive"))
    )
    (net (code "67") (name "/NTC1+") (class "Default")
      (node (ref "C34") (pin "2") (pinfunction "2_2") (pintype "passive"))
      (node (ref "C38") (pin "1") (pinfunction "1_1") (pintype "passive"))
      (node (ref "R30") (pin "1") (pinfunction "1_1") (pintype "passive"))
      (node (ref "R34") (pin "1") (pinfunction "1_1") (pintype "passive"))
    )
    (net (code "68") (name "/NTC2+") (class "Default")
      (node (ref "C35") (pin "2") (pinfunction "2_2") (pintype "passive"))
      (node (ref "C39") (pin "1") (pinfunction "1_1") (pintype "passive"))
      (node (ref "R31") (pin "1") (pinfunction "1_1") (pintype "passive"))
      (node (ref "R35") (pin "1") (pinfunction "1_1") (pintype "passive"))
    )
    (net (code "69") (name "/NTC3+") (class "Default")
      (node (ref "C37") (pin "2") (pinfunction "2_2") (pintype "passive"))
      (node (ref "C40") (pin "1") (pinfunction "1_1") (pintype "passive"))
      (node (ref "R32") (pin "1") (pinfunction "1_1") (pintype "passive"))
      (node (ref "R36") (pin "1") (pinfunction "1_1") (pintype "passive"))
    )
    (net (code "70") (name "/NTC4+") (class "Default")
      (node (ref "C36") (pin "2") (pinfunction "2_2") (pintype "passive"))
      (node (ref "C41") (pin "1") (pinfunction "1_1") (pintype "passive"))
      (node (ref "R33") (pin "1") (pinfunction "1_1") (pintype "passive"))
      (node (ref "R37") (pin "1") (pinfunction "1_1") (pintype "passive"))
    )
    (net (code "71") (name "/VBATCELL") (class "Default")
      (node (ref "C47") (pin "1") (pinfunction "1_1") (pintype "passive"))
      (node (ref "FB16") (pin "2") (pinfunction "2_2") (pintype "passive"))
      (node (ref "R40") (pin "2") (pinfunction "2_2") (pintype "passive"))
    )
    (net (code "72") (name "/VBATUP") (class "Default")
      (node (ref "R41") (pin "2") (pinfunction "2_2") (pintype "passive"))
    )
    (net (code "73") (name "GND") (class "Default")
      (node (ref "C10") (pin "2") (pinfunction "2_2") (pintype "passive"))
      (node (ref "C11") (pin "2") (pinfunction "2_2") (pintype "passive"))
      (node (ref "C12") (pin "2") (pinfunction "2_2") (pintype "passive"))
      (node (ref "C13") (pin "2") (pinfunction "2_2") (pintype "passive"))
      (node (ref "C14") (pin "2") (pinfunction "2_2") (pintype "passive"))
      (node (ref "C15") (pin "2") (pinfunction "2_2") (pintype "passive"))
      (node (ref "C16") (pin "2") (pinfunction "2_2") (pintype "passive"))
      (node (ref "C17") (pin "2") (pinfunction "2_2") (pintype "passive"))
      (node (ref "C18") (pin "2") (pinfunction "2_2") (pintype "passive"))
      (node (ref "C19") (pin "2") (pinfunction "2_2") (pintype "passive"))
      (node (ref "C24") (pin "2") (pinfunction "2_2") (pintype "passive"))
      (node (ref "C25") (pin "2") (pinfunction "2_2") (pintype "passive"))
      (node (ref "C26") (pin "2") (pinfunction "2_2") (pintype "passive"))
      (node (ref "C27") (pin "2") (pinfunction "2_2") (pintype "passive"))
      (node (ref "C28") (pin "2") (pinfunction "2_2") (pintype "passive"))
      (node (ref "C30") (pin "2") (pinfunction "2_2") (pintype "passive"))
      (node (ref "C31") (pin "2") (pinfunction "2_2") (pintype "passive"))
      (node (ref "C32") (pin "2") (pinfunction "2_2") (pintype "passive"))
      (node (ref "C33") (pin "2") (pinfunction "2_2") (pintype "passive"))
      (node (ref "C38") (pin "2") (pinfunction "2_2") (pintype "passive"))
      (node (ref "C39") (pin "2") (pinfunction "2_2") (pintype "passive"))
      (node (ref "C40") (pin "2") (pinfunction "2_2") (pintype "passive"))
      (node (ref "C41") (pin "2") (pinfunction "2_2") (pintype "passive"))
      (node (ref "C45") (pin "2") (pinfunction "2_2") (pintype "passive"))
      (node (ref "C46") (pin "2") (pinfunction "2_2") (pintype "passive"))
      (node (ref "C47") (pin "2") (pinfunction "2_2") (pintype "passive"))
      (node (ref "C48") (pin "2") (pinfunction "2_2") (pintype "passive"))
      (node (ref "C49") (pin "2") (pinfunction "2_2") (pintype "passive"))
      (node (ref "C50") (pin "2") (pinfunction "2_2") (pintype "passive"))
      (node (ref "C51") (pin "2") (pinfunction "2_2") (pintype "passive"))
      (node (ref "C52") (pin "2") (pinfunction "2_2") (pintype "passive"))
      (node (ref "C53") (pin "1") (pinfunction "1_1") (pintype "passive"))
      (node (ref "C54") (pin "1") (pinfunction "1_1") (pintype "passive"))
      (node (ref "C55") (pin "1") (pinfunction "1_1") (pintype "passive"))
      (node (ref "C59") (pin "1") (pinfunction "1_1") (pintype "passive"))
      (node (ref "D2") (pin "A") (pinfunction "A_A") (pintype "passive"))
      (node (ref "IC1") (pin "22") (pinfunction "AGND_1_22") (pintype "bidirectional"))
      (node (ref "IC1") (pin "25") (pinfunction "GNDREF_25") (pintype "bidirectional"))
      (node (ref "IC1") (pin "6") (pinfunction "CGND_6") (pintype "bidirectional"))
      (node (ref "IC1") (pin "65") (pinfunction "AGND_2_65") (pintype "bidirectional"))
      (node (ref "IC1") (pin "9") (pinfunction "DGND_9") (pintype "bidirectional"))
      (node (ref "LED1") (pin "C@1") (pinfunction "C_C@1") (pintype "passive"))
      (node (ref "Q2") (pin "2") (pinfunction "K_2") (pintype "bidirectional"))
      (node (ref "Q2") (pin "3") (pinfunction "E_3") (pintype "bidirectional"))
      (node (ref "U1") (pin "2") (pinfunction "GND_2") (pintype "power_in"))
    )
    (net (code "74") (name "Net-(C1-Pad2)") (class "Default")
      (node (ref "C1") (pin "2") (pinfunction "2_2") (pintype "passive"))
      (node (ref "C8") (pin "1") (pinfunction "1_1") (pintype "passive"))
      (node (ref "FB3") (pin "1") (pinfunction "1_1") (pintype "passive"))
      (node (ref "R1") (pin "2") (pinfunction "2_2") (pintype "passive"))
      (node (ref "R2") (pin "2") (pinfunction "2_2") (pintype "passive"))
      (node (ref "R3") (pin "2") (pinfunction "2_2") (pintype "passive"))
    )
    (net (code "75") (name "Net-(C2-Pad1)") (class "Default")
      (node (ref "C2") (pin "1") (pinfunction "1_1") (pintype "passive"))
      (node (ref "C3") (pin "2") (pinfunction "2_2") (pintype "passive"))
      (node (ref "FB5") (pin "1") (pinfunction "1_1") (pintype "passive"))
      (node (ref "R5") (pin "2") (pinfunction "2_2") (pintype "passive"))
      (node (ref "R6") (pin "2") (pinfunction "2_2") (pintype "passive"))
      (node (ref "R7") (pin "2") (pinfunction "2_2") (pintype "passive"))
    )
    (net (code "76") (name "Net-(C4-Pad1)") (class "Default")
      (node (ref "C4") (pin "1") (pinfunction "1_1") (pintype "passive"))
      (node (ref "C5") (pin "2") (pinfunction "2_2") (pintype "passive"))
      (node (ref "FB7") (pin "1") (pinfunction "1_1") (pintype "passive"))
      (node (ref "R10") (pin "2") (pinfunction "2_2") (pintype "passive"))
      (node (ref "R8") (pin "2") (pinfunction "2_2") (pintype "passive"))
      (node (ref "R9") (pin "2") (pinfunction "2_2") (pintype "passive"))
    )
    (net (code "77") (name "Net-(C6-Pad1)") (class "Default")
      (node (ref "C6") (pin "1") (pinfunction "1_1") (pintype "passive"))
      (node (ref "C7") (pin "2") (pinfunction "2_2") (pintype "passive"))
      (node (ref "FB9") (pin "1") (pinfunction "1_1") (pintype "passive"))
      (node (ref "R13") (pin "2") (pinfunction "2_2") (pintype "passive"))
      (node (ref "R14") (pin "2") (pinfunction "2_2") (pintype "passive"))
      (node (ref "R15") (pin "2") (pinfunction "2_2") (pintype "passive"))
    )
    (net (code "78") (name "Net-(C20-Pad2)") (class "Default")
      (node (ref "C20") (pin "2") (pinfunction "2_2") (pintype "passive"))
      (node (ref "C29") (pin "1") (pinfunction "1_1") (pintype "passive"))
      (node (ref "FB11") (pin "1") (pinfunction "1_1") (pintype "passive"))
      (node (ref "R20") (pin "2") (pinfunction "2_2") (pintype "passive"))
      (node (ref "R21") (pin "2") (pinfunction "2_2") (pintype "passive"))
      (node (ref "R22") (pin "2") (pinfunction "2_2") (pintype "passive"))
    )
    (net (code "79") (name "Net-(C21-Pad1)") (class "Default")
      (node (ref "C21") (pin "1") (pinfunction "1_1") (pintype "passive"))
      (node (ref "C22") (pin "2") (pinfunction "2_2") (pintype "passive"))
      (node (ref "FB13") (pin "1") (pinfunction "1_1") (pintype "passive"))
      (node (ref "R23") (pin "2") (pinfunction "2_2") (pintype "passive"))
      (node (ref "R24") (pin "2") (pinfunction "2_2") (pintype "passive"))
      (node (ref "R25") (pin "2") (pinfunction "2_2") (pintype "passive"))
    )
    (net (code "80") (name "Net-(C23-Pad1)") (class "Default")
      (node (ref "C23") (pin "1") (pinfunction "1_1") (pintype "passive"))
      (node (ref "FB15") (pin "1") (pinfunction "1_1") (pintype "passive"))
      (node (ref "R28") (pin "2") (pinfunction "2_2") (pintype "passive"))
      (node (ref "R29") (pin "2") (pinfunction "2_2") (pintype "passive"))
    )
    (net (code "81") (name "Net-(C34-Pad1)") (class "Default")
      (node (ref "C34") (pin "1") (pinfunction "1_1") (pintype "passive"))
      (node (ref "C35") (pin "1") (pinfunction "1_1") (pintype "passive"))
      (node (ref "C36") (pin "1") (pinfunction "1_1") (pintype "passive"))
      (node (ref "C37") (pin "1") (pinfunction "1_1") (pintype "passive"))
      (node (ref "R34") (pin "2") (pinfunction "2_2") (pintype "passive"))
      (node (ref "R35") (pin "2") (pinfunction "2_2") (pintype "passive"))
      (node (ref "R36") (pin "2") (pinfunction "2_2") (pintype "passive"))
      (node (ref "R37") (pin "2") (pinfunction "2_2") (pintype "passive"))
    )
    (net (code "82") (name "Net-(C54-Pad2)") (class "Default")
      (node (ref "C54") (pin "2") (pinfunction "2_2") (pintype "passive"))
      (node (ref "R44") (pin "1") (pinfunction "1_1") (pintype "passive"))
      (node (ref "R45") (pin "2") (pinfunction "2_2") (pintype "passive"))
    )
    (net (code "83") (name "Net-(C58-Pad2)") (class "Default")
      (node (ref "C58") (pin "2") (pinfunction "2_2") (pintype "passive"))
      (node (ref "R46") (pin "1") (pinfunction "1_1") (pintype "passive"))
      (node (ref "R47") (pin "2") (pinfunction "2_2") (pintype "passive"))
    )
    (net (code "84") (name "Net-(LED1-A)") (class "Default")
      (node (ref "LED1") (pin "A@1") (pinfunction "A_A@1") (pintype "passive"))
      (node (ref "R43") (pin "1") (pinfunction "1_1") (pintype "passive"))
    )
    (net (code "85") (name "Net-(Q2-A)") (class "Default")
      (node (ref "Q2") (pin "1") (pinfunction "A_1") (pintype "bidirectional"))
      (node (ref "R50") (pin "2") (pinfunction "2_2") (pintype "passive"))
    )
    (net (code "86") (name "Net-(Q2-C)") (class "Default")
      (node (ref "Q2") (pin "4") (pinfunction "C_4") (pintype "bidirectional"))
      (node (ref "R51") (pin "1") (pinfunction "1_1") (pintype "passive"))
    )
    (net (code "87") (name "Net-(U1-I{slash}O1)") (class "Default")
      (node (ref "T1") (pin "3") (pinfunction "3_3") (pintype "passive"))
      (node (ref "U1") (pin "6") (pinfunction "I/O1_6") (pintype "bidirectional"))
    )
    (net (code "88") (name "Net-(U1-I{slash}O2)") (class "Default")
      (node (ref "T1") (pin "4") (pinfunction "4_4") (pintype "passive"))
      (node (ref "U1") (pin "4") (pinfunction "I/O2_4") (pintype "bidirectional"))
    )
    (net (code "89") (name "Net-(U1-VBUS)") (class "Default")
      (node (ref "C55") (pin "2") (pinfunction "2_2") (pintype "passive"))
      (node (ref "U1") (pin "5") (pinfunction "VBUS_5") (pintype "power_in"))
    )
    (net (code "90") (name "Net-(U2-GND)") (class "Default")
      (node (ref "C56") (pin "2") (pinfunction "2_2") (pintype "passive"))
      (node (ref "C57") (pin "1") (pinfunction "1_1") (pintype "passive"))
      (node (ref "C58") (pin "1") (pinfunction "1_1") (pintype "passive"))
      (node (ref "U2") (pin "2") (pinfunction "GND_2") (pintype "power_in"))
    )
    (net (code "91") (name "Net-(U2-I{slash}O1_2)") (class "Default")
      (node (ref "C56") (pin "1") (pinfunction "1_1") (pintype "passive"))
      (node (ref "R46") (pin "2") (pinfunction "2_2") (pintype "passive"))
      (node (ref "R49") (pin "1") (pinfunction "1_1") (pintype "passive"))
      (node (ref "U2") (pin "1") (pinfunction "I/O1_2_1") (pintype "bidirectional"))
    )
    (net (code "92") (name "Net-(U2-I{slash}O2_2)") (class "Default")
      (node (ref "C57") (pin "2") (pinfunction "2_2") (pintype "passive"))
      (node (ref "R47") (pin "1") (pinfunction "1_1") (pintype "passive"))
      (node (ref "R48") (pin "1") (pinfunction "1_1") (pintype "passive"))
      (node (ref "U2") (pin "3") (pinfunction "I/O2_2_3") (pintype "bidirectional"))
    )
    (net (code "93") (name "Net-(U2-VBUS)") (class "Default")
      (node (ref "C59") (pin "2") (pinfunction "2_2") (pintype "passive"))
      (node (ref "U2") (pin "5") (pinfunction "VBUS_5") (pintype "power_in"))
    )
    (net (code "94") (name "unconnected-(IC1-CAP1-Pad64)") (class "Default")
      (node (ref "IC1") (pin "64") (pinfunction "CAP1_64") (pintype "bidirectional"))
    )
    (net (code "95") (name "unconnected-(IC1-CAP2-Pad63)") (class "Default")
      (node (ref "IC1") (pin "63") (pinfunction "CAP2_63") (pintype "bidirectional"))
    )
    (net (code "96") (name "unconnected-(IC1-GPIO1__FAULTH-Pad10)") (class "Default")
      (node (ref "IC1") (pin "10") (pinfunction "GPIO1__FAULTH_10") (pintype "bidirectional"))
    )
    (net (code "97") (name "unconnected-(IC1-GPIO2__FAULTL-Pad11)") (class "Default")
      (node (ref "IC1") (pin "11") (pinfunction "GPIO2__FAULTL_11") (pintype "bidirectional"))
    )
    (net (code "98") (name "unconnected-(IC1-GPIO7__WAKEUP-Pad16)") (class "Default")
      (node (ref "IC1") (pin "16") (pinfunction "GPIO7__WAKEUP_16") (pintype "bidirectional"))
    )
    (net (code "99") (name "unconnected-(IC1-GPIO8__SCK-Pad1)") (class "Default")
      (node (ref "IC1") (pin "1") (pinfunction "GPIO8__SCK_1") (pintype "bidirectional"))
    )
    (net (code "100") (name "unconnected-(IC1-GPIO9__SDO-Pad2)") (class "Default")
      (node (ref "IC1") (pin "2") (pinfunction "GPIO9__SDO_2") (pintype "bidirectional"))
    )
    (net (code "101") (name "unconnected-(IC1-SPIEN-Pad20)") (class "Default")
      (node (ref "IC1") (pin "20") (pinfunction "SPIEN_20") (pintype "bidirectional"))
    )
    (net (code "102") (name "unconnected-(IC1-VANA-Pad21)") (class "Default")
      (node (ref "IC1") (pin "21") (pinfunction "VANA_21") (pintype "bidirectional"))
    )
    (net (code "103") (name "unconnected-(IC1-VCOM-Pad5)") (class "Default")
      (node (ref "IC1") (pin "5") (pinfunction "VCOM_5") (pintype "bidirectional"))
    )
    (net (code "104") (name "unconnected-(IC1-VREG-Pad18)") (class "Default")
      (node (ref "IC1") (pin "18") (pinfunction "VREG_18") (pintype "bidirectional"))
    )
    (net (code "105") (name "unconnected-(IC1-VTREF-Pad19)") (class "Default")
      (node (ref "IC1") (pin "19") (pinfunction "VTREF_19") (pintype "bidirectional"))
    )
    (net (code "106") (name "unconnected-(R50-Pad1)") (class "Default")
      (node (ref "R50") (pin "1") (pinfunction "1_1") (pintype "passive"))
    )
    (net (code "107") (name "unconnected-(R51-Pad2)") (class "Default")
      (node (ref "R51") (pin "2") (pinfunction "2_2") (pintype "passive"))
    )
    (net (code "108") (name "unconnected-(T1-Pad1)") (class "Default")
      (node (ref "T1") (pin "1") (pinfunction "1_1") (pintype "passive"))
    )
    (net (code "109") (name "unconnected-(T1-Pad2)") (class "Default")
      (node (ref "T1") (pin "2") (pinfunction "2_2") (pintype "passive"))
    )
    (net (code "110") (name "unconnected-(U2-I{slash}O1-Pad6)") (class "Default")
      (node (ref "U2") (pin "6") (pinfunction "I/O1_6") (pintype "bidirectional"))
    )
    (net (code "111") (name "unconnected-(U2-I{slash}O2-Pad4)") (class "Default")
      (node (ref "U2") (pin "4") (pinfunction "I/O2_4") (pintype "bidirectional"))
    )
  )
)
